# Converter.net
KiCad netlist of a schematic drawn in Altium Designer
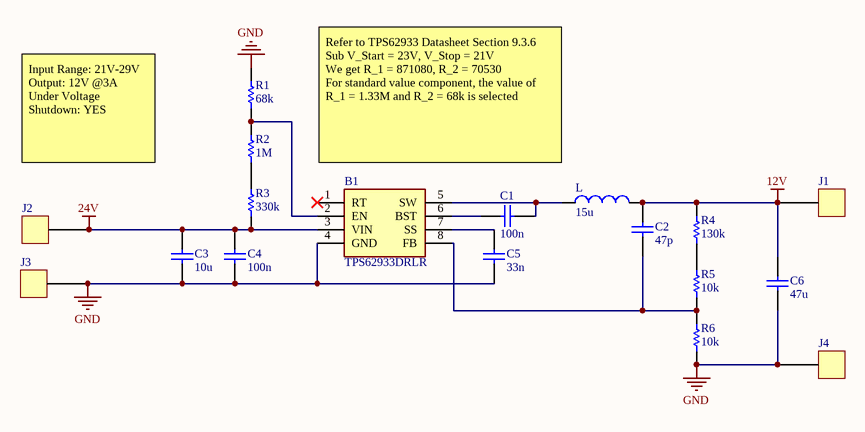
[diagram p0: Converter.SchDoc]

(export (version "E")
  (design (tool "Eeschema 10.0.6"))
  (components
    (comp (ref "B1")
      (value "TPS62933DRLR")
      (footprint "SOT583_TPS62933")
      (fields (field (name "MOUSER PART NUMBER") "595-TPS62933DRLR"))
      (libsource (lib "BMS_ShareComponentLibrary") (part "TPS62933DRLR"))
    )
    (comp (ref "C1")
      (value "100n")
      (footprint "0603_SMD_C")
      (description "0603 SMD Capacitor")
      (libsource (lib "BMS_ShareComponentLibrary") (part "0603_SMD_Capacitor"))
    )
    (comp (ref "C2")
      (value "47p")
      (footprint "0603_SMD_C")
      (description "0603 SMD Capacitor")
      (libsource (lib "BMS_ShareComponentLibrary") (part "0603_SMD_Capacitor"))
    )
    (comp (ref "C3")
      (value "10u")
      (footprint "1206_SMD_C")
      (description "1206 SMD Capacitor")
      (libsource (lib "BMS_ShareComponentLibrary") (part "1206_SMD_Capacitor"))
    )
    (comp (ref "C4")
      (value "100n")
      (footprint "0805_SMD_C")
      (description "0805 SMD Capacitor")
      (libsource (lib "BMS_ShareComponentLibrary") (part "0805_SMD_Capacitor"))
    )
    (comp (ref "C5")
      (value "33n")
      (footprint "0603_SMD_C")
      (description "0603 SMD Capacitor")
      (libsource (lib "BMS_ShareComponentLibrary") (part "0603_SMD_Capacitor"))
    )
    (comp (ref "C6")
      (value "47u")
      (footprint "1210_SMD_C")
      (description "1210 SMD Capacitor")
      (libsource (lib "BMS_ShareComponentLibrary") (part "1210_SMD_Capacitor"))
    )
    (comp (ref "J1")
      (value "CastellatedHoles")
      (footprint "CastellatedHole")
      (libsource (lib "BMS_ShareComponentLibrary") (part "CastellatedHoles"))
    )
    (comp (ref "J2")
      (value "CastellatedHoles")
      (footprint "CastellatedHole")
      (libsource (lib "") (part "CastellatedHoles_1"))
    )
    (comp (ref "J3")
      (value "CastellatedHoles")
      (footprint "CastellatedHole")
      (libsource (lib "") (part "CastellatedHoles_1"))
    )
    (comp (ref "J4")
      (value "CastellatedHoles")
      (footprint "CastellatedHole")
      (libsource (lib "BMS_ShareComponentLibrary") (part "CastellatedHoles"))
    )
    (comp (ref "L")
      (value "15u")
      (footprint "DR127_SMD_L")
      (description "15ÂµH Shielded Wirewound Inductor 5.03A 24.7mOhm Nonstandard")
      (fields (field (name "MP") "DR127-150-R") (field (name "MF") "Coiltronics"))
      (libsource (lib "BMS_ShareComponentLibrary") (part "DR127-150-R"))
    )
    (comp (ref "R1")
      (value "68k")
      (footprint "0603_SMD_R")
      (description "0603 SMD Resistor")
      (libsource (lib "BMS_ShareComponentLibrary") (part "0603_SMD_Resistor"))
    )
    (comp (ref "R2")
      (value "1M")
      (footprint "0603_SMD_R")
      (description "0603 SMD Resistor")
      (libsource (lib "BMS_ShareComponentLibrary") (part "0603_SMD_Resistor"))
    )
    (comp (ref "R3")
      (value "330k")
      (footprint "0603_SMD_R")
      (description "0603 SMD Resistor")
      (libsource (lib "BMS_ShareComponentLibrary") (part "0603_SMD_Resistor"))
    )
    (comp (ref "R4")
      (value "130k")
      (footprint "0603_SMD_R")
      (description "0603 SMD Resistor")
      (libsource (lib "BMS_ShareComponentLibrary") (part "0603_SMD_Resistor"))
    )
    (comp (ref "R5")
      (value "10k")
      (footprint "0603_SMD_R")
      (description "0603 SMD Resistor")
      (libsource (lib "BMS_ShareComponentLibrary") (part "0603_SMD_Resistor"))
    )
    (comp (ref "R6")
      (value "10k")
      (footprint "0603_SMD_R")
      (description "0603 SMD Resistor")
      (libsource (lib "BMS_ShareComponentLibrary") (part "0603_SMD_Resistor"))
    )
  )
  (nets
    (net (code "1") (name "12V") (class "Default")
      (node (ref "C2") (pin "2") (pinfunction "2_2") (pintype "passive"))
      (node (ref "C6") (pin "2") (pinfunction "2_2") (pintype "passive"))
      (node (ref "J1") (pin "1") (pinfunction "1_1") (pintype "passive"))
      (node (ref "L") (pin "1") (pinfunction "1_1") (pintype "passive"))
      (node (ref "R4") (pin "2") (pinfunction "2_2") (pintype "passive"))
    )
    (net (code "2") (name "24V") (class "Default")
      (node (ref "B1") (pin "3") (pinfunction "VIN_3") (pintype "passive"))
      (node (ref "C3") (pin "2") (pinfunction "2_2") (pintype "passive"))
      (node (ref "C4") (pin "2") (pinfunction "2_2") (pintype "passive"))
      (node (ref "J2") (pin "1") (pinfunction "1_1") (pintype "passive"))
      (node (ref "R3") (pin "1") (pinfunction "1_1") (pintype "passive"))
    )
    (net (code "3") (name "GND") (class "Default")
      (node (ref "B1") (pin "4") (pinfunction "GND_4") (pintype "passive"))
      (node (ref "C3") (pin "1") (pinfunction "1_1") (pintype "passive"))
      (node (ref "C4") (pin "1") (pinfunction "1_1") (pintype "passive"))
      (node (ref "C5") (pin "1") (pinfunction "1_1") (pintype "passive"))
      (node (ref "C6") (pin "1") (pinfunction "1_1") (pintype "passive"))
      (node (ref "J3") (pin "1") (pinfunction "1_1") (pintype "passive"))
      (node (ref "J4") (pin "1") (pinfunction "1_1") (pintype "passive"))
      (node (ref "R1") (pin "2") (pinfunction "2_2") (pintype "passive"))
      (node (ref "R6") (pin "1") (pinfunction "1_1") (pintype "passive"))
    )
    (net (code "4") (name "Net-(B1-BST)") (class "Default")
      (node (ref "B1") (pin "6") (pinfunction "BST_6") (pintype "passive"))
      (node (ref "C1") (pin "1") (pinfunction "1_1") (pintype "passive"))
    )
    (net (code "5") (name "Net-(B1-EN)") (class "Default")
      (node (ref "B1") (pin "2") (pinfunction "EN_2") (pintype "passive"))
      (node (ref "R1") (pin "1") (pinfunction "1_1") (pintype "passive"))
      (node (ref "R2") (pin "2") (pinfunction "2_2") (pintype "passive"))
    )
    (net (code "6") (name "Net-(B1-FB)") (class "Default")
      (node (ref "B1") (pin "8") (pinfunction "FB_8") (pintype "passive"))
      (node (ref "C2") (pin "1") (pinfunction "1_1") (pintype "passive"))
      (node (ref "R5") (pin "1") (pinfunction "1_1") (pintype "passive"))
      (node (ref "R6") (pin "2") (pinfunction "2_2") (pintype "passive"))
    )
    (net (code "7") (name "Net-(B1-SS)") (class "Default")
      (node (ref "B1") (pin "7") (pinfunction "SS_7") (pintype "passive"))
      (node (ref "C5") (pin "2") (pinfunction "2_2") (pintype "passive"))
    )
    (net (code "8") (name "Net-(B1-SW)") (class "Default")
      (node (ref "B1") (pin "5") (pinfunction "SW_5") (pintype "passive"))
      (node (ref "C1") (pin "2") (pinfunction "2_2") (pintype "passive"))
      (node (ref "L") (pin "2") (pinfunction "2_2") (pintype "passive"))
    )
    (net (code "9") (name "Net-(R2-Pad1)") (class "Default")
      (node (ref "R2") (pin "1") (pinfunction "1_1") (pintype "passive"))
      (node (ref "R3") (pin "2") (pinfunction "2_2") (pintype "passive"))
    )
    (net (code "10") (name "Net-(R4-Pad1)") (class "Default")
      (node (ref "R4") (pin "1") (pinfunction "1_1") (pintype "passive"))
      (node (ref "R5") (pin "2") (pinfunction "2_2") (pintype "passive"))
    )
    (net (code "11") (name "unconnected-(B1-RT-Pad1)") (class "Default")
      (node (ref "B1") (pin "1") (pinfunction "RT_1") (pintype "passive+no_connect"))
    )
  )
)
